# esp32_artnet_pinball.net
KiCad netlist of a schematic drawn in EAGLE
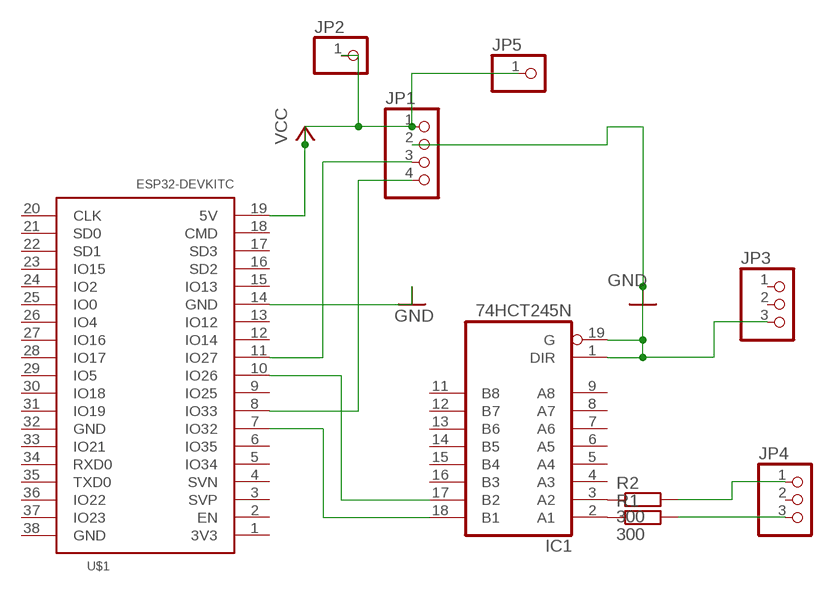
[diagram p0: schematic, sheet 1]

(export (version "E")
  (design (tool "Eeschema 10.0.6"))
  (components
    (comp (ref "IC1")
      (value "74HCT245N")
      (footprint "eagle-import:DIL20")
      (libsource (lib "eagle-import") (part "74245NHCT"))
    )
    (comp (ref "JP1")
      (value "PINHD-1X4")
      (footprint "eagle-import:1X04")
      (libsource (lib "eagle-import") (part "PINHD-1X4"))
    )
    (comp (ref "JP2")
      (value "PINHD-1X1")
      (footprint "eagle-import:1X01")
      (libsource (lib "eagle-import") (part "PINHD-1X1"))
    )
    (comp (ref "JP3")
      (value "PINHD-1X3")
      (footprint "eagle-import:1X03")
      (libsource (lib "eagle-import") (part "PINHD-1X3"))
    )
    (comp (ref "JP4")
      (value "PINHD-1X3")
      (footprint "eagle-import:1X03")
      (libsource (lib "eagle-import") (part "PINHD-1X3"))
    )
    (comp (ref "JP5")
      (value "PINHD-1X1")
      (footprint "eagle-import:1X01")
      (libsource (lib "eagle-import") (part "PINHD-1X1"))
    )
    (comp (ref "R1")
      (value "300")
      (footprint "eagle-import:R1206")
      (libsource (lib "eagle-import") (part "R-EU_R1206"))
    )
    (comp (ref "R2")
      (value "300")
      (footprint "eagle-import:R1206")
      (libsource (lib "eagle-import") (part "R-EU_R1206"))
    )
    (comp (ref "U$1")
      (value "ESP32DEVKITC")
      (footprint "eagle-import:ESP32-DEVKITC")
      (libsource (lib "eagle-import") (part "ESP32DEVKITC"))
    )
  )
  (nets
    (net (code "1") (name "GND") (class "Default")
      (node (ref "IC1") (pin "1") (pinfunction "DIR_1") (pintype "input"))
      (node (ref "IC1") (pin "19") (pinfunction "G_19") (pintype "input"))
      (node (ref "JP1") (pin "2") (pinfunction "2_2") (pintype "passive"))
      (node (ref "JP3") (pin "3") (pinfunction "3_3") (pintype "passive"))
      (node (ref "U$1") (pin "14") (pinfunction "GND_14") (pintype "bidirectional"))
    )
    (net (code "2") (name "Net-(IC1A-A1)") (class "Default")
      (node (ref "IC1") (pin "2") (pinfunction "A1_2") (pintype "bidirectional"))
      (node (ref "R1") (pin "1") (pinfunction "1_1") (pintype "passive"))
    )
    (net (code "3") (name "Net-(IC1A-A2)") (class "Default")
      (node (ref "IC1") (pin "3") (pinfunction "A2_3") (pintype "bidirectional"))
      (node (ref "R2") (pin "1") (pinfunction "1_1") (pintype "passive"))
    )
    (net (code "4") (name "Net-(IC1A-B1)") (class "Default")
      (node (ref "IC1") (pin "18") (pinfunction "B1_18") (pintype "bidirectional"))
      (node (ref "U$1") (pin "7") (pinfunction "IO32_7") (pintype "bidirectional"))
    )
    (net (code "5") (name "Net-(IC1A-B2)") (class "Default")
      (node (ref "IC1") (pin "17") (pinfunction "B2_17") (pintype "bidirectional"))
      (node (ref "U$1") (pin "10") (pinfunction "IO26_10") (pintype "bidirectional"))
    )
    (net (code "6") (name "Net-(JP4-Pad1)") (class "Default")
      (node (ref "JP4") (pin "1") (pinfunction "1_1") (pintype "passive"))
      (node (ref "R2") (pin "2") (pinfunction "2_2") (pintype "passive"))
    )
    (net (code "7") (name "Net-(JP4-Pad3)") (class "Default")
      (node (ref "JP4") (pin "3") (pinfunction "3_3") (pintype "passive"))
      (node (ref "R1") (pin "2") (pinfunction "2_2") (pintype "passive"))
    )
    (net (code "8") (name "Net-(U$1-IO27)") (class "Default")
      (node (ref "JP1") (pin "3") (pinfunction "3_3") (pintype "passive"))
      (node (ref "U$1") (pin "11") (pinfunction "IO27_11") (pintype "bidirectional"))
    )
    (net (code "9") (name "Net-(U$1-IO33)") (class "Default")
      (node (ref "JP1") (pin "4") (pinfunction "4_4") (pintype "passive"))
      (node (ref "U$1") (pin "8") (pinfunction "IO33_8") (pintype "bidirectional"))
    )
    (net (code "10") (name "VCC") (class "Default")
      (node (ref "JP1") (pin "1") (pinfunction "1_1") (pintype "passive"))
      (node (ref "JP2") (pin "1") (pinfunction "1_1") (pintype "passive"))
      (node (ref "JP5") (pin "1") (pinfunction "1_1") (pintype "passive"))
      (node (ref "U$1") (pin "19") (pinfunction "5V_19") (pintype "bidirectional"))
    )
    (net (code "11") (name "unconnected-(IC1A-A3-Pad4)") (class "Default")
      (node (ref "IC1") (pin "4") (pinfunction "A3_4") (pintype "bidirectional"))
    )
    (net (code "12") (name "unconnected-(IC1A-A4-Pad5)") (class "Default")
      (node (ref "IC1") (pin "5") (pinfunction "A4_5") (pintype "bidirectional"))
    )
    (net (code "13") (name "unconnected-(IC1A-A5-Pad6)") (class "Default")
      (node (ref "IC1") (pin "6") (pinfunction "A5_6") (pintype "bidirectional"))
    )
    (net (code "14") (name "unconnected-(IC1A-A6-Pad7)") (class "Default")
      (node (ref "IC1") (pin "7") (pinfunction "A6_7") (pintype "bidirectional"))
    )
    (net (code "15") (name "unconnected-(IC1A-A7-Pad8)") (class "Default")
      (node (ref "IC1") (pin "8") (pinfunction "A7_8") (pintype "bidirectional"))
    )
    (net (code "16") (name "unconnected-(IC1A-A8-Pad9)") (class "Default")
      (node (ref "IC1") (pin "9") (pinfunction "A8_9") (pintype "bidirectional"))
    )
    (net (code "17") (name "unconnected-(IC1A-B3-Pad16)") (class "Default")
      (node (ref "IC1") (pin "16") (pinfunction "B3_16") (pintype "bidirectional"))
    )
    (net (code "18") (name "unconnected-(IC1A-B4-Pad15)") (class "Default")
      (node (ref "IC1") (pin "15") (pinfunction "B4_15") (pintype "bidirectional"))
    )
    (net (code "19") (name "unconnected-(IC1A-B5-Pad14)") (class "Default")
      (node (ref "IC1") (pin "14") (pinfunction "B5_14") (pintype "bidirectional"))
    )
    (net (code "20") (name "unconnected-(IC1A-B6-Pad13)") (class "Default")
      (node (ref "IC1") (pin "13") (pinfunction "B6_13") (pintype "bidirectional"))
    )
    (net (code "21") (name "unconnected-(IC1A-B7-Pad12)") (class "Default")
      (node (ref "IC1") (pin "12") (pinfunction "B7_12") (pintype "bidirectional"))
    )
    (net (code "22") (name "unconnected-(IC1A-B8-Pad11)") (class "Default")
      (node (ref "IC1") (pin "11") (pinfunction "B8_11") (pintype "bidirectional"))
    )
    (net (code "23") (name "unconnected-(JP3-Pad1)") (class "Default")
      (node (ref "JP3") (pin "1") (pinfunction "1_1") (pintype "passive"))
    )
    (net (code "24") (name "unconnected-(JP3-Pad2)") (class "Default")
      (node (ref "JP3") (pin "2") (pinfunction "2_2") (pintype "passive"))
    )
    (net (code "25") (name "unconnected-(JP4-Pad2)") (class "Default")
      (node (ref "JP4") (pin "2") (pinfunction "2_2") (pintype "passive"))
    )
    (net (code "26") (name "unconnected-(U$1-3V3-Pad1)") (class "Default")
      (node (ref "U$1") (pin "1") (pinfunction "3V3_1") (pintype "bidirectional"))
    )
    (net (code "27") (name "unconnected-(U$1-CLK-Pad20)") (class "Default")
      (node (ref "U$1") (pin "20") (pinfunction "CLK_20") (pintype "bidirectional"))
    )
    (net (code "28") (name "unconnected-(U$1-CMD-Pad18)") (class "Default")
      (node (ref "U$1") (pin "18") (pinfunction "CMD_18") (pintype "bidirectional"))
    )
    (net (code "29") (name "unconnected-(U$1-EN-Pad2)") (class "Default")
      (node (ref "U$1") (pin "2") (pinfunction "EN_2") (pintype "bidirectional"))
    )
    (net (code "30") (name "unconnected-(U$1-GND-Pad32)") (class "Default")
      (node (ref "U$1") (pin "32") (pinfunction "GND_32") (pintype "bidirectional"))
    )
    (net (code "31") (name "unconnected-(U$1-GND-Pad38)") (class "Default")
      (node (ref "U$1") (pin "38") (pinfunction "GND_38") (pintype "bidirectional"))
    )
    (net (code "32") (name "unconnected-(U$1-IO0-Pad25)") (class "Default")
      (node (ref "U$1") (pin "25") (pinfunction "IO0_25") (pintype "bidirectional"))
    )
    (net (code "33") (name "unconnected-(U$1-IO2-Pad24)") (class "Default")
      (node (ref "U$1") (pin "24") (pinfunction "IO2_24") (pintype "bidirectional"))
    )
    (net (code "34") (name "unconnected-(U$1-IO4-Pad26)") (class "Default")
      (node (ref "U$1") (pin "26") (pinfunction "IO4_26") (pintype "bidirectional"))
    )
    (net (code "35") (name "unconnected-(U$1-IO5-Pad29)") (class "Default")
      (node (ref "U$1") (pin "29") (pinfunction "IO5_29") (pintype "bidirectional"))
    )
    (net (code "36") (name "unconnected-(U$1-IO12-Pad13)") (class "Default")
      (node (ref "U$1") (pin "13") (pinfunction "IO12_13") (pintype "bidirectional"))
    )
    (net (code "37") (name "unconnected-(U$1-IO13-Pad15)") (class "Default")
      (node (ref "U$1") (pin "15") (pinfunction "IO13_15") (pintype "bidirectional"))
    )
    (net (code "38") (name "unconnected-(U$1-IO14-Pad12)") (class "Default")
      (node (ref "U$1") (pin "12") (pinfunction "IO14_12") (pintype "bidirectional"))
    )
    (net (code "39") (name "unconnected-(U$1-IO15-Pad23)") (class "Default")
      (node (ref "U$1") (pin "23") (pinfunction "IO15_23") (pintype "bidirectional"))
    )
    (net (code "40") (name "unconnected-(U$1-IO16-Pad27)") (class "Default")
      (node (ref "U$1") (pin "27") (pinfunction "IO16_27") (pintype "bidirectional"))
    )
    (net (code "41") (name "unconnected-(U$1-IO17-Pad28)") (class "Default")
      (node (ref "U$1") (pin "28") (pinfunction "IO17_28") (pintype "bidirectional"))
    )
    (net (code "42") (name "unconnected-(U$1-IO18-Pad30)") (class "Default")
      (node (ref "U$1") (pin "30") (pinfunction "IO18_30") (pintype "bidirectional"))
    )
    (net (code "43") (name "unconnected-(U$1-IO19-Pad31)") (class "Default")
      (node (ref "U$1") (pin "31") (pinfunction "IO19_31") (pintype "bidirectional"))
    )
    (net (code "44") (name "unconnected-(U$1-IO21-Pad33)") (class "Default")
      (node (ref "U$1") (pin "33") (pinfunction "IO21_33") (pintype "bidirectional"))
    )
    (net (code "45") (name "unconnected-(U$1-IO22-Pad36)") (class "Default")
      (node (ref "U$1") (pin "36") (pinfunction "IO22_36") (pintype "bidirectional"))
    )
    (net (code "46") (name "unconnected-(U$1-IO23-Pad37)") (class "Default")
      (node (ref "U$1") (pin "37") (pinfunction "IO23_37") (pintype "bidirectional"))
    )
    (net (code "47") (name "unconnected-(U$1-IO25-Pad9)") (class "Default")
      (node (ref "U$1") (pin "9") (pinfunction "IO25_9") (pintype "bidirectional"))
    )
    (net (code "48") (name "unconnected-(U$1-IO34-Pad5)") (class "Default")
      (node (ref "U$1") (pin "5") (pinfunction "IO34_5") (pintype "bidirectional"))
    )
    (net (code "49") (name "unconnected-(U$1-IO35-Pad6)") (class "Default")
      (node (ref "U$1") (pin "6") (pinfunction "IO35_6") (pintype "bidirectional"))
    )
    (net (code "50") (name "unconnected-(U$1-RXD0-Pad34)") (class "Default")
      (node (ref "U$1") (pin "34") (pinfunction "RXD0_34") (pintype "bidirectional"))
    )
    (net (code "51") (name "unconnected-(U$1-SD0-Pad21)") (class "Default")
      (node (ref "U$1") (pin "21") (pinfunction "SD0_21") (pintype "bidirectional"))
    )
    (net (code "52") (name "unconnected-(U$1-SD1-Pad22)") (class "Default")
      (node (ref "U$1") (pin "22") (pinfunction "SD1_22") (pintype "bidirectional"))
    )
    (net (code "53") (name "unconnected-(U$1-SD2-Pad16)") (class "Default")
      (node (ref "U$1") (pin "16") (pinfunction "SD2_16") (pintype "bidirectional"))
    )
    (net (code "54") (name "unconnected-(U$1-SD3-Pad17)") (class "Default")
      (node (ref "U$1") (pin "17") (pinfunction "SD3_17") (pintype "bidirectional"))
    )
    (net (code "55") (name "unconnected-(U$1-SVN-Pad4)") (class "Default")
      (node (ref "U$1") (pin "4") (pinfunction "SVN_4") (pintype "bidirectional"))
    )
    (net (code "56") (name "unconnected-(U$1-SVP-Pad3)") (class "Default")
      (node (ref "U$1") (pin "3") (pinfunction "SVP_3") (pintype "bidirectional"))
    )
    (net (code "57") (name "unconnected-(U$1-TXD0-Pad35)") (class "Default")
      (node (ref "U$1") (pin "35") (pinfunction "TXD0_35") (pintype "bidirectional"))
    )
  )
)
